# femtoBeacon_dongle_r2_0_4_RGB.net
KiCad netlist of a schematic drawn in EAGLE
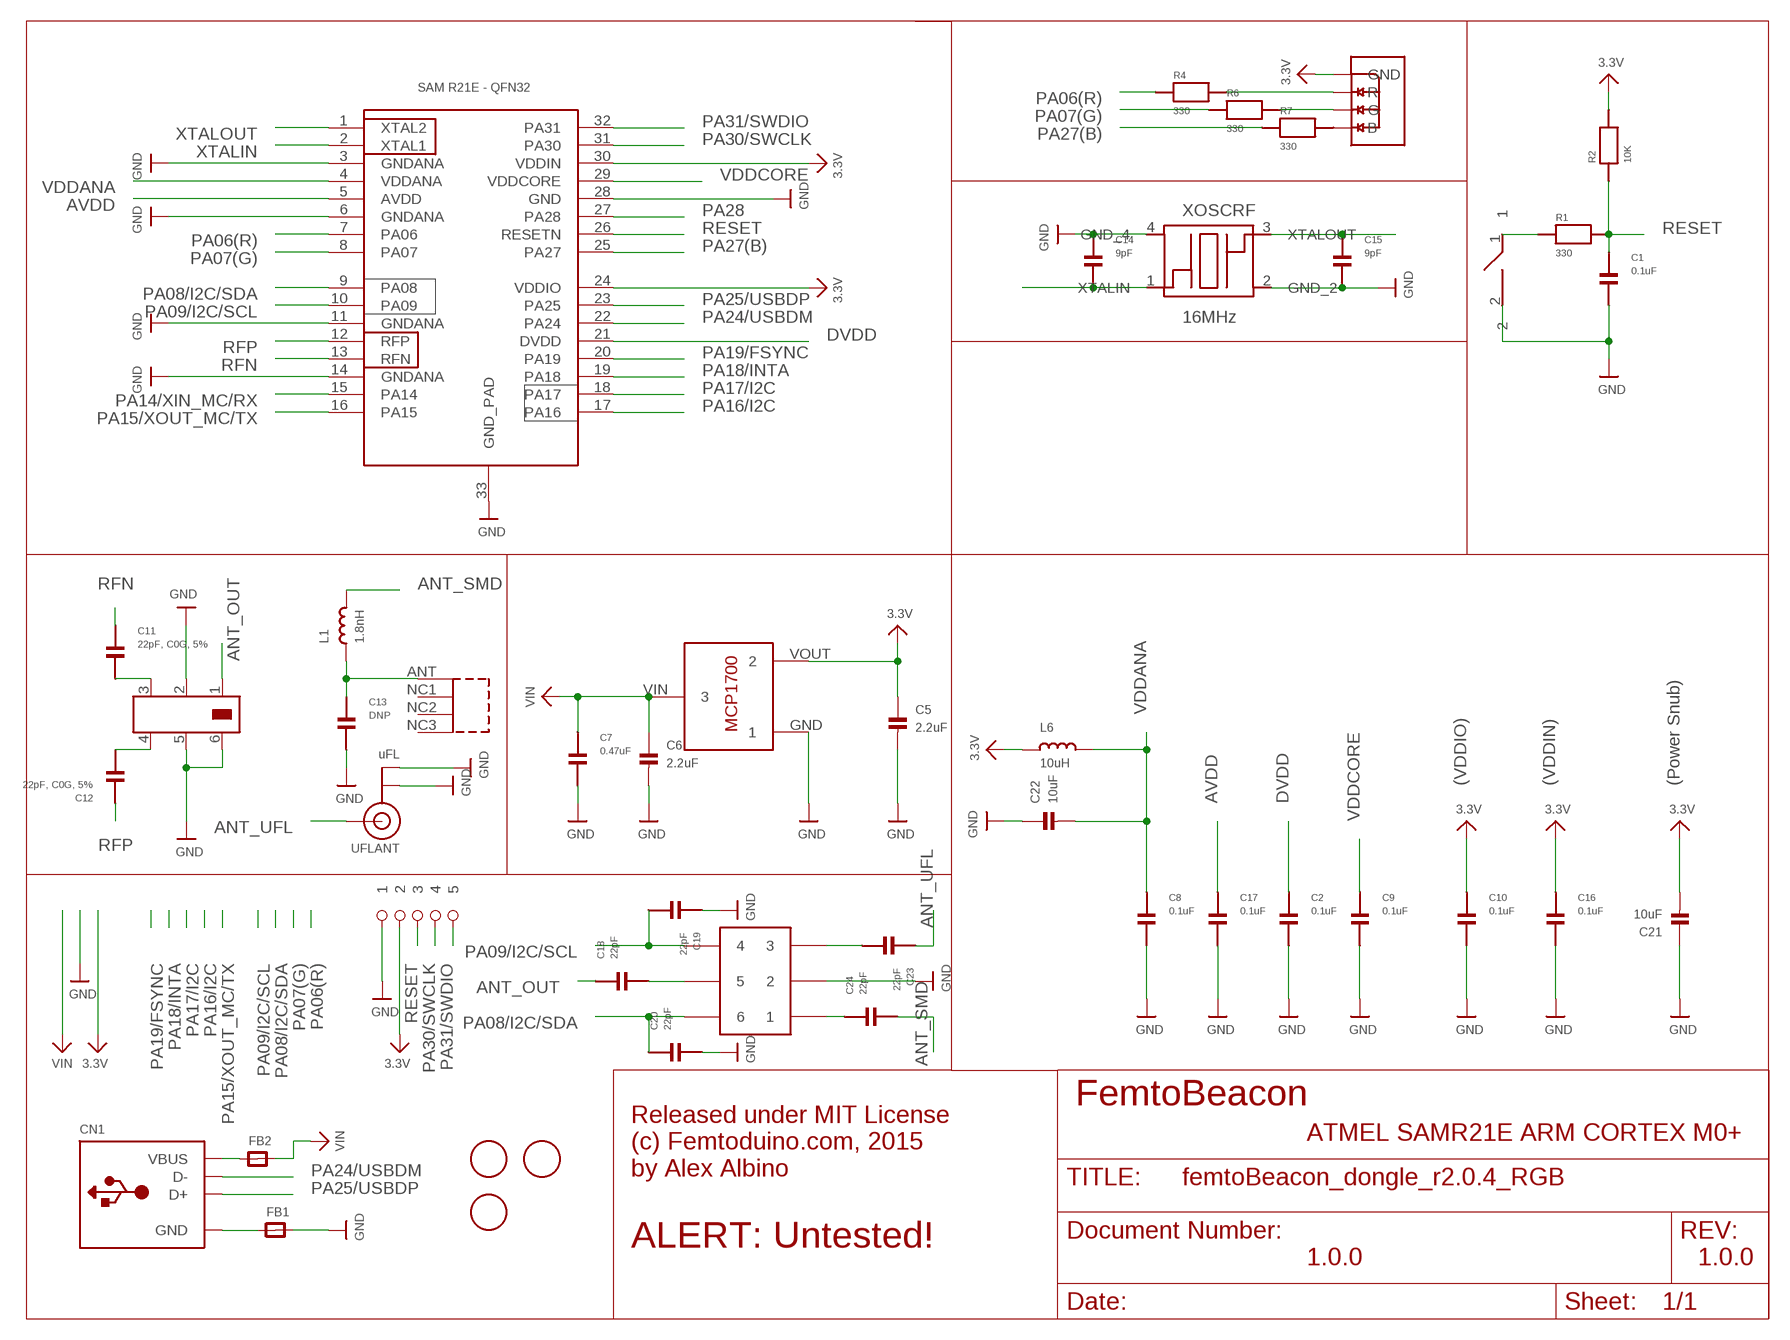
[diagram p0: schematic, sheet 1]

(export (version "E")
  (design (tool "Eeschema 10.0.6"))
  (components
    (comp (ref "ASWITCH")
      (value "AS222-92LF")
      (footprint "eagle-import:AS222-92LF")
      (libsource (lib "eagle-import") (part "AS222-92LF"))
    )
    (comp (ref "BTN")
      (value "DNP")
      (footprint "eagle-import:SPST_SMD")
      (libsource (lib "eagle-import") (part "SPST_SMD"))
    )
    (comp (ref "C1")
      (value "0.1uF")
      (footprint "eagle-import:PART")
      (fields (field (name "DIGIKEY_PART") "490-3194-1-ND"))
      (libsource (lib "eagle-import") (part "CAPACITOR_0201"))
    )
    (comp (ref "C2")
      (value "0.1uF")
      (footprint "eagle-import:PART")
      (libsource (lib "eagle-import") (part "CAPACITOR_0201"))
    )
    (comp (ref "C5")
      (value "2.2uF")
      (footprint "eagle-import:_0402MP")
      (libsource (lib "eagle-import") (part "CAP_CERAMIC_0402MP"))
    )
    (comp (ref "C6")
      (value "2.2uF")
      (footprint "eagle-import:_0402MP")
      (libsource (lib "eagle-import") (part "CAP_CERAMIC_0402MP"))
    )
    (comp (ref "C7")
      (value "0.47uF")
      (footprint "eagle-import:PART")
      (libsource (lib "eagle-import") (part "CAPACITOR_0201"))
    )
    (comp (ref "C8")
      (value "0.1uF")
      (footprint "eagle-import:PART")
      (fields (field (name "DIGIKEY_PART") "490-3194-1-ND"))
      (libsource (lib "eagle-import") (part "CAPACITOR_0201"))
    )
    (comp (ref "C9")
      (value "0.1uF")
      (footprint "eagle-import:PART")
      (fields (field (name "DIGIKEY_PART") "490-3194-1-ND"))
      (libsource (lib "eagle-import") (part "CAPACITOR_0201"))
    )
    (comp (ref "C10")
      (value "0.1uF")
      (footprint "eagle-import:PART")
      (fields (field (name "DIGIKEY_PART") "490-3194-1-ND"))
      (libsource (lib "eagle-import") (part "CAPACITOR_0201"))
    )
    (comp (ref "C11")
      (value "22pF, C0G, 5%")
      (footprint "eagle-import:PART")
      (fields (field (name "DIGIKEY_PART") "490-3194-1-ND"))
      (libsource (lib "eagle-import") (part "CAPACITOR_0201"))
    )
    (comp (ref "C12")
      (value "22pF, C0G, 5%")
      (footprint "eagle-import:PART")
      (fields (field (name "DIGIKEY_PART") "490-3194-1-ND"))
      (libsource (lib "eagle-import") (part "CAPACITOR_0201"))
    )
    (comp (ref "C13")
      (value "DNP")
      (footprint "eagle-import:PART")
      (fields (field (name "DIGIKEY_PART") "490-3194-1-ND"))
      (libsource (lib "eagle-import") (part "CAPACITOR_0201"))
    )
    (comp (ref "C14")
      (value "9pF")
      (footprint "eagle-import:PART")
      (fields (field (name "DIGIKEY_PART") "490-3194-1-ND"))
      (libsource (lib "eagle-import") (part "CAPACITOR_0201"))
    )
    (comp (ref "C15")
      (value "9pF")
      (footprint "eagle-import:PART")
      (fields (field (name "DIGIKEY_PART") "490-3194-1-ND"))
      (libsource (lib "eagle-import") (part "CAPACITOR_0201"))
    )
    (comp (ref "C16")
      (value "0.1uF")
      (footprint "eagle-import:PART")
      (fields (field (name "DIGIKEY_PART") "490-3194-1-ND"))
      (libsource (lib "eagle-import") (part "CAPACITOR_0201"))
    )
    (comp (ref "C17")
      (value "0.1uF")
      (footprint "eagle-import:PART")
      (fields (field (name "DIGIKEY_PART") "490-3194-1-ND"))
      (libsource (lib "eagle-import") (part "CAPACITOR_0201"))
    )
    (comp (ref "C18")
      (value "22pF")
      (footprint "eagle-import:PART")
      (fields (field (name "DIGIKEY_PART") "490-3194-1-ND"))
      (libsource (lib "eagle-import") (part "CAPACITOR_0201"))
    )
    (comp (ref "C19")
      (value "22pF")
      (footprint "eagle-import:PART")
      (fields (field (name "DIGIKEY_PART") "490-3194-1-ND"))
      (libsource (lib "eagle-import") (part "CAPACITOR_0201"))
    )
    (comp (ref "C20")
      (value "22pF")
      (footprint "eagle-import:PART")
      (fields (field (name "DIGIKEY_PART") "490-3194-1-ND"))
      (libsource (lib "eagle-import") (part "CAPACITOR_0201"))
    )
    (comp (ref "C21")
      (value "10uF")
      (footprint "eagle-import:_0402MP")
      (libsource (lib "eagle-import") (part "CAP_CERAMIC_0402MP"))
    )
    (comp (ref "C22")
      (value "10uF")
      (footprint "eagle-import:_0402MP")
      (libsource (lib "eagle-import") (part "CAP_CERAMIC_0402MP"))
    )
    (comp (ref "C23")
      (value "22pF")
      (footprint "eagle-import:PART")
      (fields (field (name "DIGIKEY_PART") "490-3194-1-ND"))
      (libsource (lib "eagle-import") (part "CAPACITOR_0201"))
    )
    (comp (ref "C24")
      (value "22pF")
      (footprint "eagle-import:PART")
      (fields (field (name "DIGIKEY_PART") "490-3194-1-ND"))
      (libsource (lib "eagle-import") (part "CAPACITOR_0201"))
    )
    (comp (ref "CN1")
      (value "USB_TYPEA")
      (footprint "eagle-import:USB_A-SMT")
      (libsource (lib "eagle-import") (part "USB_TYPEA"))
    )
    (comp (ref "FB1")
      (value "FERRITE_0603MP")
      (footprint "eagle-import:_0603MP")
      (libsource (lib "eagle-import") (part "FERRITE_0603MP"))
    )
    (comp (ref "FB2")
      (value "FERRITE_0603MP")
      (footprint "eagle-import:_0603MP")
      (libsource (lib "eagle-import") (part "FERRITE_0603MP"))
    )
    (comp (ref "FID1")
      (value "FIDUCIAL")
      (footprint "eagle-import:FIDUCIAL_1MM")
      (libsource (lib "eagle-import") (part "FIDUCIAL"))
    )
    (comp (ref "FID2")
      (value "FIDUCIAL")
      (footprint "eagle-import:FIDUCIAL_1MM")
      (libsource (lib "eagle-import") (part "FIDUCIAL"))
    )
    (comp (ref "FID3")
      (value "FIDUCIAL")
      (footprint "eagle-import:FIDUCIAL_1MM")
      (libsource (lib "eagle-import") (part "FIDUCIAL"))
    )
    (comp (ref "L1")
      (value "1.8nH")
      (footprint "eagle-import:_0603MP")
      (libsource (lib "eagle-import") (part "INDUCTOR_0603MP"))
    )
    (comp (ref "L6")
      (value "10uH")
      (footprint "eagle-import:_0603MP")
      (libsource (lib "eagle-import") (part "INDUCTOR_0603MP"))
    )
    (comp (ref "LDO_VREG")
      (value "MCP1700T-3302E/TT")
      (footprint "eagle-import:MCP1700T-3302E_TT")
      (libsource (lib "eagle-import") (part "MCP1700T-3302E/TT"))
    )
    (comp (ref "R1")
      (value "330")
      (footprint "eagle-import:PART")
      (libsource (lib "eagle-import") (part "RESISTOR_0201"))
    )
    (comp (ref "R2")
      (value "10K")
      (footprint "eagle-import:PART")
      (libsource (lib "eagle-import") (part "RESISTOR_0201"))
    )
    (comp (ref "R4")
      (value "330")
      (footprint "eagle-import:PART")
      (libsource (lib "eagle-import") (part "RESISTOR_0201"))
    )
    (comp (ref "R6")
      (value "330")
      (footprint "eagle-import:PART")
      (libsource (lib "eagle-import") (part "RESISTOR_0201"))
    )
    (comp (ref "R7")
      (value "330")
      (footprint "eagle-import:PART")
      (libsource (lib "eagle-import") (part "RESISTOR_0201"))
    )
    (comp (ref "RGBLED")
      (value "LRTB_R48G")
      (footprint "eagle-import:LRTB_R48G")
      (libsource (lib "eagle-import") (part "LRTB_R48G"))
    )
    (comp (ref "U$1")
      (value "1X5_ROUND")
      (footprint "eagle-import:1X5_ROUND")
      (libsource (lib "eagle-import") (part "1X5_ROUND"))
    )
    (comp (ref "U$6")
      (value "0479480001")
      (footprint "eagle-import:0479480001")
      (libsource (lib "eagle-import") (part "0479480001"))
    )
    (comp (ref "U$12")
      (value "JOHANSON_2450BM15A0015E")
      (footprint "eagle-import:0805_BALUN")
      (libsource (lib "eagle-import") (part "JOHANSON_2450BM15A0015E"))
    )
    (comp (ref "U$76")
      (value "ATSAMR21E18A-MUT")
      (footprint "eagle-import:QFN32")
      (libsource (lib "eagle-import") (part "ATSAMR21E18A-MUT"))
    )
    (comp (ref "UFLANT")
      (value "uFL")
      (footprint "eagle-import:U.FL")
      (libsource (lib "eagle-import") (part "ANTENNA_U.FL"))
    )
    (comp (ref "XOSCRF")
      (value "16MHz")
      (footprint "eagle-import:TSX-3225")
      (libsource (lib "eagle-import") (part "TSX-3225"))
    )
  )
  (nets
    (net (code "1") (name "/ANT_OUT") (class "Default")
      (node (ref "C18") (pin "1") (pinfunction "P$1_1") (pintype "bidirectional"))
      (node (ref "U$12") (pin "1") (pinfunction "1_1") (pintype "bidirectional"))
    )
    (net (code "2") (name "/ANT_SMD") (class "Default")
      (node (ref "C24") (pin "2") (pinfunction "P$2_2") (pintype "bidirectional"))
      (node (ref "L1") (pin "2") (pinfunction "2_2") (pintype "passive"))
    )
    (net (code "3") (name "/ANT_UFL") (class "Default")
      (node (ref "C23") (pin "1") (pinfunction "P$1_1") (pintype "bidirectional"))
      (node (ref "UFLANT") (pin "3") (pinfunction "SIGNAL_3") (pintype "passive"))
    )
    (net (code "4") (name "/AVDD") (class "Default")
      (node (ref "C17") (pin "1") (pinfunction "P$1_1") (pintype "bidirectional"))
      (node (ref "U$76") (pin "5") (pinfunction "AVDD_5") (pintype "bidirectional"))
    )
    (net (code "5") (name "/DVDD") (class "Default")
      (node (ref "C2") (pin "1") (pinfunction "P$1_1") (pintype "bidirectional"))
      (node (ref "U$76") (pin "21") (pinfunction "DVDD_21") (pintype "bidirectional"))
    )
    (net (code "6") (name "/PA06(R)") (class "Default")
      (node (ref "R4") (pin "1") (pinfunction "1_1") (pintype "bidirectional"))
      (node (ref "U$76") (pin "7") (pinfunction "PA06_7") (pintype "bidirectional"))
    )
    (net (code "7") (name "/PA07(G)") (class "Default")
      (node (ref "R6") (pin "1") (pinfunction "1_1") (pintype "bidirectional"))
      (node (ref "U$76") (pin "8") (pinfunction "PA07_8") (pintype "bidirectional"))
    )
    (net (code "8") (name "/PA08{slash}I2C{slash}SDA") (class "Default")
      (node (ref "ASWITCH") (pin "PIN6") (pinfunction "6_PIN6") (pintype "bidirectional"))
      (node (ref "C20") (pin "1") (pinfunction "P$1_1") (pintype "bidirectional"))
      (node (ref "U$76") (pin "9") (pinfunction "PA08_9") (pintype "bidirectional"))
    )
    (net (code "9") (name "/PA09{slash}I2C{slash}SCL") (class "Default")
      (node (ref "ASWITCH") (pin "PIN4") (pinfunction "4_PIN4") (pintype "bidirectional"))
      (node (ref "C19") (pin "2") (pinfunction "P$2_2") (pintype "bidirectional"))
      (node (ref "U$76") (pin "10") (pinfunction "PA09_10") (pintype "bidirectional"))
    )
    (net (code "10") (name "/PA14{slash}XIN_MC{slash}RX") (class "Default")
      (node (ref "U$76") (pin "15") (pinfunction "PA14_15") (pintype "bidirectional"))
    )
    (net (code "11") (name "/PA15{slash}XOUT_MC{slash}TX") (class "Default")
      (node (ref "U$76") (pin "16") (pinfunction "PA15_16") (pintype "bidirectional"))
    )
    (net (code "12") (name "/PA16{slash}I2C") (class "Default")
      (node (ref "U$76") (pin "17") (pinfunction "PA16_17") (pintype "bidirectional"))
    )
    (net (code "13") (name "/PA17{slash}I2C") (class "Default")
      (node (ref "U$76") (pin "18") (pinfunction "PA17_18") (pintype "bidirectional"))
    )
    (net (code "14") (name "/PA18{slash}INTA") (class "Default")
      (node (ref "U$76") (pin "19") (pinfunction "PA18_19") (pintype "bidirectional"))
    )
    (net (code "15") (name "/PA19{slash}FSYNC") (class "Default")
      (node (ref "U$76") (pin "20") (pinfunction "PA19_20") (pintype "bidirectional"))
    )
    (net (code "16") (name "/PA24{slash}USBDM") (class "Default")
      (node (ref "CN1") (pin "D-") (pinfunction "D-_D-") (pintype "bidirectional"))
      (node (ref "U$76") (pin "22") (pinfunction "PA24_22") (pintype "bidirectional"))
    )
    (net (code "17") (name "/PA25{slash}USBDP") (class "Default")
      (node (ref "CN1") (pin "D+") (pinfunction "D+_D+") (pintype "bidirectional"))
      (node (ref "U$76") (pin "23") (pinfunction "PA25_23") (pintype "bidirectional"))
    )
    (net (code "18") (name "/PA27(B)") (class "Default")
      (node (ref "R7") (pin "1") (pinfunction "1_1") (pintype "bidirectional"))
      (node (ref "U$76") (pin "25") (pinfunction "PA27_25") (pintype "bidirectional"))
    )
    (net (code "19") (name "/PA28") (class "Default")
      (node (ref "U$76") (pin "27") (pinfunction "PA28_27") (pintype "bidirectional"))
    )
    (net (code "20") (name "/PA30{slash}SWCLK") (class "Default")
      (node (ref "U$1") (pin "P$4") (pinfunction "4_P$4") (pintype "bidirectional"))
      (node (ref "U$76") (pin "31") (pinfunction "PA30_31") (pintype "bidirectional"))
    )
    (net (code "21") (name "/PA31{slash}SWDIO") (class "Default")
      (node (ref "U$1") (pin "P$5") (pinfunction "5_P$5") (pintype "bidirectional"))
      (node (ref "U$76") (pin "32") (pinfunction "PA31_32") (pintype "bidirectional"))
    )
    (net (code "22") (name "/RESET") (class "Default")
      (node (ref "C1") (pin "1") (pinfunction "P$1_1") (pintype "bidirectional"))
      (node (ref "R1") (pin "2") (pinfunction "2_2") (pintype "bidirectional"))
      (node (ref "R2") (pin "1") (pinfunction "1_1") (pintype "bidirectional"))
      (node (ref "U$1") (pin "P$3") (pinfunction "3_P$3") (pintype "bidirectional"))
      (node (ref "U$76") (pin "26") (pinfunction "RESETN_26") (pintype "bidirectional"))
    )
    (net (code "23") (name "/RFN") (class "Default")
      (node (ref "C11") (pin "1") (pinfunction "P$1_1") (pintype "bidirectional"))
      (node (ref "U$76") (pin "13") (pinfunction "RFN_13") (pintype "bidirectional"))
    )
    (net (code "24") (name "/RFP") (class "Default")
      (node (ref "C12") (pin "1") (pinfunction "P$1_1") (pintype "bidirectional"))
      (node (ref "U$76") (pin "12") (pinfunction "RFP_12") (pintype "bidirectional"))
    )
    (net (code "25") (name "/VDDANA") (class "Default")
      (node (ref "C22") (pin "2") (pinfunction "P$2_2") (pintype "passive"))
      (node (ref "C8") (pin "1") (pinfunction "P$1_1") (pintype "bidirectional"))
      (node (ref "L6") (pin "2") (pinfunction "2_2") (pintype "passive"))
      (node (ref "U$76") (pin "4") (pinfunction "VDDANA_4") (pintype "bidirectional"))
    )
    (net (code "26") (name "/VDDCORE") (class "Default")
      (node (ref "C9") (pin "1") (pinfunction "P$1_1") (pintype "bidirectional"))
      (node (ref "U$76") (pin "29") (pinfunction "VDDCORE_29") (pintype "bidirectional"))
    )
    (net (code "27") (name "/XTALIN") (class "Default")
      (node (ref "C14") (pin "2") (pinfunction "P$2_2") (pintype "bidirectional"))
      (node (ref "U$76") (pin "2") (pinfunction "XTAL1_2") (pintype "bidirectional"))
      (node (ref "XOSCRF") (pin "1") (pinfunction "XTALIN_1") (pintype "bidirectional"))
    )
    (net (code "28") (name "/XTALOUT") (class "Default")
      (node (ref "C15") (pin "1") (pinfunction "P$1_1") (pintype "bidirectional"))
      (node (ref "U$76") (pin "1") (pinfunction "XTAL2_1") (pintype "bidirectional"))
      (node (ref "XOSCRF") (pin "3") (pinfunction "XTALOUT_3") (pintype "bidirectional"))
    )
    (net (code "29") (name "3.3V") (class "Default")
      (node (ref "C10") (pin "1") (pinfunction "P$1_1") (pintype "bidirectional"))
      (node (ref "C16") (pin "1") (pinfunction "P$1_1") (pintype "bidirectional"))
      (node (ref "C21") (pin "2") (pinfunction "P$2_2") (pintype "passive"))
      (node (ref "C5") (pin "1") (pinfunction "P$1_1") (pintype "passive"))
      (node (ref "L6") (pin "1") (pinfunction "1_1") (pintype "passive"))
      (node (ref "LDO_VREG") (pin "VOUT") (pinfunction "2_VOUT") (pintype "bidirectional"))
      (node (ref "R2") (pin "2") (pinfunction "2_2") (pintype "bidirectional"))
      (node (ref "RGBLED") (pin "1") (pinfunction "GND_1") (pintype "bidirectional"))
      (node (ref "U$1") (pin "P$2") (pinfunction "2_P$2") (pintype "bidirectional"))
      (node (ref "U$76") (pin "24") (pinfunction "VDDIO_24") (pintype "bidirectional"))
      (node (ref "U$76") (pin "30") (pinfunction "VDDIN_30") (pintype "bidirectional"))
    )
    (net (code "30") (name "GND") (class "Default")
      (node (ref "ASWITCH") (pin "PIN2") (pinfunction "2_PIN2") (pintype "bidirectional"))
      (node (ref "BTN") (pin "2") (pinfunction "2_2") (pintype "bidirectional"))
      (node (ref "C1") (pin "2") (pinfunction "P$2_2") (pintype "bidirectional"))
      (node (ref "C10") (pin "2") (pinfunction "P$2_2") (pintype "bidirectional"))
      (node (ref "C13") (pin "2") (pinfunction "P$2_2") (pintype "bidirectional"))
      (node (ref "C14") (pin "1") (pinfunction "P$1_1") (pintype "bidirectional"))
      (node (ref "C15") (pin "2") (pinfunction "P$2_2") (pintype "bidirectional"))
      (node (ref "C16") (pin "2") (pinfunction "P$2_2") (pintype "bidirectional"))
      (node (ref "C17") (pin "2") (pinfunction "P$2_2") (pintype "bidirectional"))
      (node (ref "C19") (pin "1") (pinfunction "P$1_1") (pintype "bidirectional"))
      (node (ref "C2") (pin "2") (pinfunction "P$2_2") (pintype "bidirectional"))
      (node (ref "C20") (pin "2") (pinfunction "P$2_2") (pintype "bidirectional"))
      (node (ref "C21") (pin "1") (pinfunction "P$1_1") (pintype "passive"))
      (node (ref "C22") (pin "1") (pinfunction "P$1_1") (pintype "passive"))
      (node (ref "C5") (pin "2") (pinfunction "P$2_2") (pintype "passive"))
      (node (ref "C6") (pin "2") (pinfunction "P$2_2") (pintype "passive"))
      (node (ref "C7") (pin "2") (pinfunction "P$2_2") (pintype "bidirectional"))
      (node (ref "C8") (pin "2") (pinfunction "P$2_2") (pintype "bidirectional"))
      (node (ref "C9") (pin "2") (pinfunction "P$2_2") (pintype "bidirectional"))
      (node (ref "FB1") (pin "2") (pinfunction "P$2_2") (pintype "passive"))
      (node (ref "LDO_VREG") (pin "GND") (pinfunction "1_GND") (pintype "bidirectional"))
      (node (ref "U$1") (pin "P$1") (pinfunction "1_P$1") (pintype "bidirectional"))
      (node (ref "U$12") (pin "2") (pinfunction "2_2") (pintype "bidirectional"))
      (node (ref "U$12") (pin "5") (pinfunction "5_5") (pintype "bidirectional"))
      (node (ref "U$12") (pin "6") (pinfunction "6_6") (pintype "bidirectional"))
      (node (ref "U$76") (pin "11") (pinfunction "GNDANA_11") (pintype "bidirectional"))
      (node (ref "U$76") (pin "14") (pinfunction "GNDANA_14") (pintype "bidirectional"))
      (node (ref "U$76") (pin "28") (pinfunction "GND_28") (pintype "bidirectional"))
      (node (ref "U$76") (pin "3") (pinfunction "GNDANA_3") (pintype "bidirectional"))
      (node (ref "U$76") (pin "33") (pinfunction "GND_PAD_33") (pintype "bidirectional"))
      (node (ref "U$76") (pin "6") (pinfunction "GNDANA_6") (pintype "bidirectional"))
      (node (ref "UFLANT") (pin "1") (pinfunction "GND_1") (pintype "passive"))
      (node (ref "UFLANT") (pin "2") (pinfunction "GND_2") (pintype "passive"))
      (node (ref "XOSCRF") (pin "2") (pinfunction "GND_2_2") (pintype "bidirectional"))
      (node (ref "XOSCRF") (pin "4") (pinfunction "GND_4_4") (pintype "bidirectional"))
    )
    (net (code "31") (name "Net-(ASWITCH-1)") (class "Default")
      (node (ref "ASWITCH") (pin "PIN1") (pinfunction "1_PIN1") (pintype "bidirectional"))
      (node (ref "C24") (pin "1") (pinfunction "P$1_1") (pintype "bidirectional"))
    )
    (net (code "32") (name "Net-(ASWITCH-3)") (class "Default")
      (node (ref "ASWITCH") (pin "PIN3") (pinfunction "3_PIN3") (pintype "bidirectional"))
      (node (ref "C23") (pin "2") (pinfunction "P$2_2") (pintype "bidirectional"))
    )
    (net (code "33") (name "Net-(ASWITCH-5)") (class "Default")
      (node (ref "ASWITCH") (pin "PIN5") (pinfunction "5_PIN5") (pintype "bidirectional"))
      (node (ref "C18") (pin "2") (pinfunction "P$2_2") (pintype "bidirectional"))
    )
    (net (code "34") (name "Net-(BTN-Pad1)") (class "Default")
      (node (ref "BTN") (pin "1") (pinfunction "1_1") (pintype "bidirectional"))
      (node (ref "R1") (pin "1") (pinfunction "1_1") (pintype "bidirectional"))
    )
    (net (code "35") (name "Net-(C11-P$2)") (class "Default")
      (node (ref "C11") (pin "2") (pinfunction "P$2_2") (pintype "bidirectional"))
      (node (ref "U$12") (pin "3") (pinfunction "3_3") (pintype "bidirectional"))
    )
    (net (code "36") (name "Net-(C12-P$2)") (class "Default")
      (node (ref "C12") (pin "2") (pinfunction "P$2_2") (pintype "bidirectional"))
      (node (ref "U$12") (pin "4") (pinfunction "4_4") (pintype "bidirectional"))
    )
    (net (code "37") (name "Net-(C13-P$1)") (class "Default")
      (node (ref "C13") (pin "1") (pinfunction "P$1_1") (pintype "bidirectional"))
      (node (ref "L1") (pin "1") (pinfunction "1_1") (pintype "passive"))
      (node (ref "U$6") (pin "ANT") (pinfunction "1_ANT") (pintype "bidirectional"))
    )
    (net (code "38") (name "Net-(FB1-P$1)") (class "Default")
      (node (ref "CN1") (pin "GND") (pinfunction "GND_GND") (pintype "power_in"))
      (node (ref "FB1") (pin "1") (pinfunction "P$1_1") (pintype "passive"))
    )
    (net (code "39") (name "Net-(FB2-P$1)") (class "Default")
      (node (ref "CN1") (pin "VBUS") (pinfunction "VBUS_VBUS") (pintype "power_in"))
      (node (ref "FB2") (pin "1") (pinfunction "P$1_1") (pintype "passive"))
    )
    (net (code "40") (name "Net-(RGBLED-B)") (class "Default")
      (node (ref "R7") (pin "2") (pinfunction "2_2") (pintype "bidirectional"))
      (node (ref "RGBLED") (pin "4") (pinfunction "B_4") (pintype "bidirectional"))
    )
    (net (code "41") (name "Net-(RGBLED-G)") (class "Default")
      (node (ref "R6") (pin "2") (pinfunction "2_2") (pintype "bidirectional"))
      (node (ref "RGBLED") (pin "3") (pinfunction "G_3") (pintype "bidirectional"))
    )
    (net (code "42") (name "Net-(RGBLED-R)") (class "Default")
      (node (ref "R4") (pin "2") (pinfunction "2_2") (pintype "bidirectional"))
      (node (ref "RGBLED") (pin "2") (pinfunction "R_2") (pintype "bidirectional"))
    )
    (net (code "43") (name "VIN") (class "Default")
      (node (ref "C6") (pin "1") (pinfunction "P$1_1") (pintype "passive"))
      (node (ref "C7") (pin "1") (pinfunction "P$1_1") (pintype "bidirectional"))
      (node (ref "FB2") (pin "2") (pinfunction "P$2_2") (pintype "passive"))
      (node (ref "LDO_VREG") (pin "VIN") (pinfunction "3_VIN") (pintype "bidirectional"))
    )
    (net (code "44") (name "unconnected-(U$6-2-PadNC1)") (class "Default")
      (node (ref "U$6") (pin "NC1") (pinfunction "2_NC1") (pintype "bidirectional"))
    )
    (net (code "45") (name "unconnected-(U$6-3-PadNC2)") (class "Default")
      (node (ref "U$6") (pin "NC2") (pinfunction "3_NC2") (pintype "bidirectional"))
    )
    (net (code "46") (name "unconnected-(U$6-4-PadNC3)") (class "Default")
      (node (ref "U$6") (pin "NC3") (pinfunction "4_NC3") (pintype "bidirectional"))
    )
  )
)
